# SeismoSpiesPCB.net
KiCad netlist of a schematic drawn in EAGLE
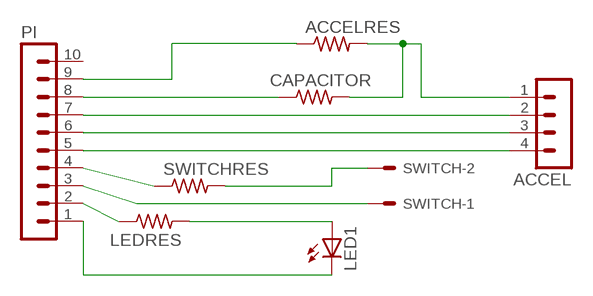
[diagram p0: schematic, sheet 1]

(export (version "E")
  (design (tool "Eeschema 10.0.6"))
  (components
    (comp (ref "ACCEL")
      (value "04_PIN-HEADER")
      (footprint "eagle-import:MA04-1")
      (libsource (lib "eagle-import") (part "04_PIN-HEADER"))
    )
    (comp (ref "ACCELRES")
      (value "4.7 K")
      (footprint "eagle-import:RESISTOR")
      (libsource (lib "eagle-import") (part "RESISTOR0204/7"))
    )
    (comp (ref "CAPACITOR")
      (value "RESISTOR0204/7")
      (footprint "eagle-import:RESISTOR")
      (libsource (lib "eagle-import") (part "RESISTOR0204/7"))
    )
    (comp (ref "LED1")
      (value "LED3MM")
      (footprint "eagle-import:LED3MM")
      (libsource (lib "eagle-import") (part "LED3MM"))
    )
    (comp (ref "LEDRES")
      (value "RESISTOR0204/7")
      (footprint "eagle-import:RESISTOR")
      (libsource (lib "eagle-import") (part "RESISTOR0204/7"))
    )
    (comp (ref "PI")
      (value "10_PIN-HEADER-(FROM_ARDUINO)")
      (footprint "eagle-import:MA10-1")
      (libsource (lib "eagle-import") (part "10_PIN-HEADER-(FROM_ARDUINO)"))
    )
    (comp (ref "SWITCH")
      (value "02_PIN-HEADER")
      (footprint "eagle-import:02_PIN")
      (libsource (lib "eagle-import") (part "02_PIN-HEADER"))
    )
    (comp (ref "SWITCHRES")
      (value "RESISTOR0204/7")
      (footprint "eagle-import:RESISTOR")
      (libsource (lib "eagle-import") (part "RESISTOR0204/7"))
    )
  )
  (nets
    (net (code "1") (name "Net-(ACCEL-Pad1)") (class "Default")
      (node (ref "ACCEL") (pin "1") (pinfunction "1_1") (pintype "passive"))
      (node (ref "ACCELRES") (pin "2") (pinfunction "2_2") (pintype "passive"))
      (node (ref "CAPACITOR") (pin "2") (pinfunction "2_2") (pintype "passive"))
    )
    (net (code "2") (name "Net-(ACCEL-Pad2)") (class "Default")
      (node (ref "ACCEL") (pin "2") (pinfunction "2_2") (pintype "passive"))
      (node (ref "PI") (pin "7") (pinfunction "7_7") (pintype "passive"))
    )
    (net (code "3") (name "Net-(ACCEL-Pad3)") (class "Default")
      (node (ref "ACCEL") (pin "3") (pinfunction "3_3") (pintype "passive"))
      (node (ref "PI") (pin "6") (pinfunction "6_6") (pintype "passive"))
    )
    (net (code "4") (name "Net-(ACCEL-Pad4)") (class "Default")
      (node (ref "ACCEL") (pin "4") (pinfunction "4_4") (pintype "passive"))
      (node (ref "PI") (pin "5") (pinfunction "5_5") (pintype "passive"))
    )
    (net (code "5") (name "Net-(ACCELRES-Pad1)") (class "Default")
      (node (ref "ACCELRES") (pin "1") (pinfunction "1_1") (pintype "passive"))
      (node (ref "PI") (pin "9") (pinfunction "9_9") (pintype "passive"))
    )
    (net (code "6") (name "Net-(CAPACITOR-Pad1)") (class "Default")
      (node (ref "CAPACITOR") (pin "1") (pinfunction "1_1") (pintype "passive"))
      (node (ref "PI") (pin "8") (pinfunction "8_8") (pintype "passive"))
    )
    (net (code "7") (name "Net-(LED1-C)") (class "Default")
      (node (ref "LED1") (pin "K") (pinfunction "C_K") (pintype "passive"))
      (node (ref "PI") (pin "1") (pinfunction "1_1") (pintype "passive"))
    )
    (net (code "8") (name "Net-(LED1-PadA)") (class "Default")
      (node (ref "LED1") (pin "A") (pinfunction "A_A") (pintype "passive"))
      (node (ref "LEDRES") (pin "2") (pinfunction "2_2") (pintype "passive"))
    )
    (net (code "9") (name "Net-(LEDRES-Pad1)") (class "Default")
      (node (ref "LEDRES") (pin "1") (pinfunction "1_1") (pintype "passive"))
      (node (ref "PI") (pin "2") (pinfunction "2_2") (pintype "passive"))
    )
    (net (code "10") (name "Net-(PI-Pad4)") (class "Default")
      (node (ref "PI") (pin "4") (pinfunction "4_4") (pintype "passive"))
      (node (ref "SWITCHRES") (pin "1") (pinfunction "1_1") (pintype "passive"))
    )
    (net (code "11") (name "Net-(SWITCHA-S)") (class "Default")
      (node (ref "PI") (pin "3") (pinfunction "3_3") (pintype "passive"))
      (node (ref "SWITCH") (pin "1") (pinfunction "S_1") (pintype "passive"))
    )
    (net (code "12") (name "Net-(SWITCHB-S)") (class "Default")
      (node (ref "SWITCH") (pin "2") (pinfunction "S_2") (pintype "passive"))
      (node (ref "SWITCHRES") (pin "2") (pinfunction "2_2") (pintype "passive"))
    )
    (net (code "13") (name "unconnected-(PI-Pad10)") (class "Default")
      (node (ref "PI") (pin "10") (pinfunction "10_10") (pintype "passive"))
    )
  )
)
